# SingleBoardTestRev1.net
KiCad netlist of a schematic drawn in Altium Designer
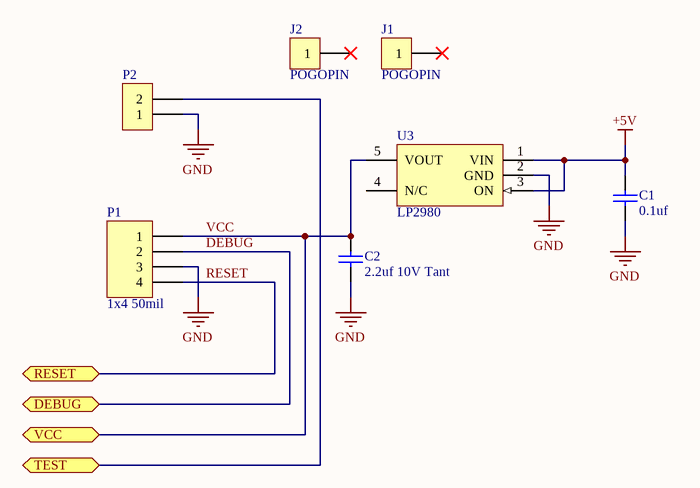
[diagram p0: SingleBoardTestRev1.SchDoc]

(export (version "E")
  (design (tool "Eeschema 10.0.6"))
  (components
    (comp (ref "C1")
      (value "0.1uf")
      (footprint "0603_072205")
      (description "Capacitor")
      (fields (field (name "PARTNO") "C0603C104Z3VACTU"))
      (libsource (lib "Miscellaneous Devices") (part "Cap"))
    )
    (comp (ref "C2")
      (value "2.2uf 10V Tant")
      (footprint "CAP A CASE_030205")
      (description "Capacitor")
      (fields (field (name "PARTNO") "F931A225MAA"))
      (libsource (lib "Miscellaneous Devices") (part "Cap"))
    )
    (comp (ref "J1")
      (value "POGOPIN")
      (footprint "TestPoint52x32")
      (description "Connector")
      (libsource (lib "Common") (part "CON1"))
    )
    (comp (ref "J2")
      (value "POGOPIN")
      (footprint "TestPoint52x32")
      (description "Connector")
      (libsource (lib "Common") (part "CON1"))
    )
    (comp (ref "P1")
      (value "1x4 50mil")
      (footprint "1X4 HEADER_50mil_071411")
      (description "Header, 4-Pin")
      (libsource (lib "Miscellaneous Connectors") (part "Header 4"))
    )
    (comp (ref "P2")
      (value "1x2 50mil")
      (footprint "1X2 HEADER_50MIL_081611")
      (libsource (lib "Common") (part "CON2"))
    )
    (comp (ref "U3")
      (value "LP2980")
      (footprint "SOT25_030205")
      (fields (field (name "PARTNO") "LP2980AIM5-3.3/NOPB"))
      (libsource (lib "Common") (part "LP2985"))
    )
  )
  (nets
    (net (code "1") (name "+5V") (class "Default")
      (node (ref "C1") (pin "1") (pinfunction "1_1") (pintype "passive"))
      (node (ref "U3") (pin "1") (pinfunction "VIN_1") (pintype "power_in"))
      (node (ref "U3") (pin "3") (pinfunction "ON_3") (pintype "input"))
    )
    (net (code "2") (name "/DEBUG") (class "Default")
      (node (ref "P1") (pin "2") (pinfunction "2_2") (pintype "passive"))
    )
    (net (code "3") (name "/RESET") (class "Default")
      (node (ref "P1") (pin "4") (pinfunction "4_4") (pintype "passive"))
    )
    (net (code "4") (name "/TEST") (class "Default")
      (node (ref "P2") (pin "2") (pinfunction "2_2") (pintype "passive"))
    )
    (net (code "5") (name "/VCC") (class "Default")
      (node (ref "C2") (pin "1") (pinfunction "1_1") (pintype "passive"))
      (node (ref "P1") (pin "1") (pinfunction "1_1") (pintype "passive"))
      (node (ref "U3") (pin "5") (pinfunction "VOUT_5") (pintype "power_in"))
    )
    (net (code "6") (name "GND") (class "Default")
      (node (ref "C1") (pin "2") (pinfunction "2_2") (pintype "passive"))
      (node (ref "C2") (pin "2") (pinfunction "2_2") (pintype "passive"))
      (node (ref "P1") (pin "3") (pinfunction "3_3") (pintype "passive"))
      (node (ref "P2") (pin "1") (pinfunction "1_1") (pintype "passive"))
      (node (ref "U3") (pin "2") (pinfunction "GND_2") (pintype "power_in"))
    )
    (net (code "7") (name "unconnected-(J1-Pad1)") (class "Default")
      (node (ref "J1") (pin "1") (pinfunction "1_1") (pintype "passive+no_connect"))
    )
    (net (code "8") (name "unconnected-(J2-Pad1)") (class "Default")
      (node (ref "J2") (pin "1") (pinfunction "1_1") (pintype "passive+no_connect"))
    )
    (net (code "9") (name "unconnected-(U3-N{slash}C-Pad4)") (class "Default")
      (node (ref "U3") (pin "4") (pinfunction "N/C_4") (pintype "passive"))
    )
  )
)
